# Detector.net
KiCad netlist of a schematic drawn in Altium Designer
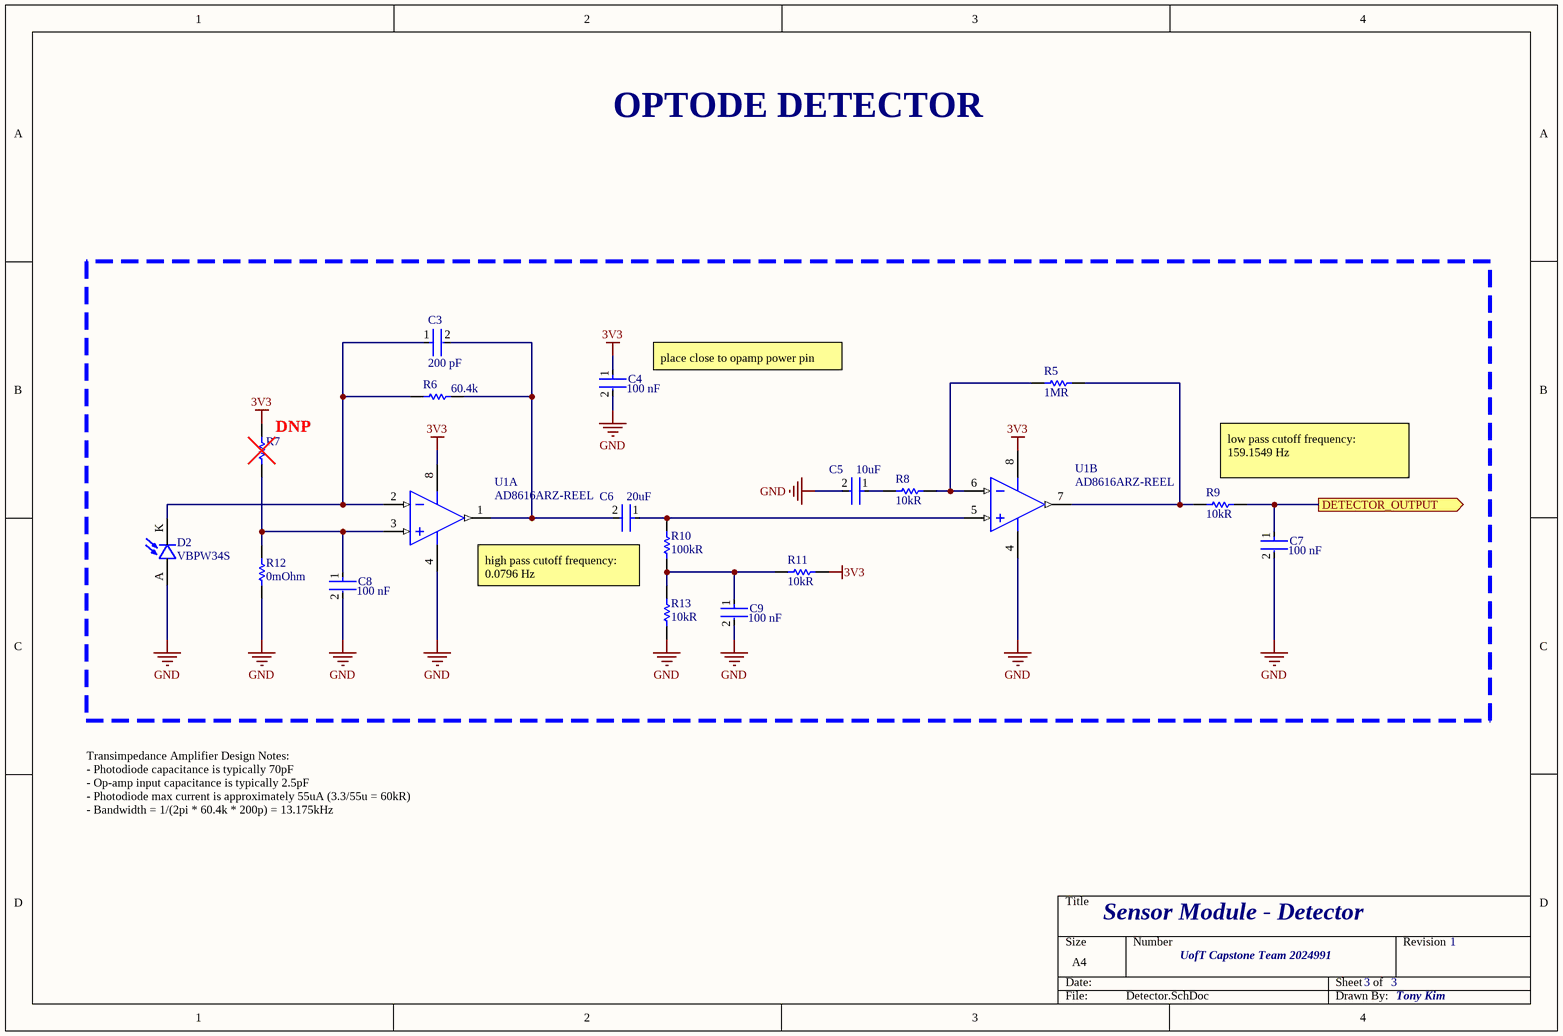
[diagram p0: Detector.SchDoc]

(export (version "E")
  (design (tool "Eeschema 10.0.6"))
  (components
    (comp (ref "C3")
      (value "C0603C201J5GACTU")
      (footprint "FP-C0603C-CF-MFG")
      (description "CAP CER 200PF 50V 5% NP0 0603")
      (fields
        (field (name "CAPACITANCE") "200 pF")
        (field (name "MANUFACTURER") "KEMET")
        (field (name "OCTOPART") "https://octopart.com/c0603c201j5gactu-kemet-9143917")
      )
      (libsource (lib "Altium Content Vault") (part "b4654b650e69147ec39a6b967a45e02"))
    )
    (comp (ref "C4")
      (value "CC0603KRX7R7BB104")
      (footprint "FP-CC0603-DA-MFG")
      (description "CAP CER 0.1UF 16V X7R 0603")
      (fields
        (field (name "OCTOPART") "https://octopart.com/cc0603krx7r7bb104-yageo-192941")
        (field (name "TOLERANCE") "0.1")
        (field (name "CAPACITANCE") "100 nF")
      )
      (libsource (lib "Altium Content Vault") (part "11868f565c42a9108669ba33697ecf6"))
    )
    (comp (ref "C5")
      (value "GRM188R60J106ME47D")
      (footprint "FP-GRM188-0_1-e0_2_0_55-IPC_C")
      (description "Chip Multilayer Ceramic Capacitors for General Purpose, 0603, 10uF, X5R, 15%, 20%, 6.3V")
      (fields
        (field (name "CAPACITANCE") "10uF")
        (field (name "VOLTAGE") "6.3V")
        (field (name "TOLERANCE") "20%")
      )
      (libsource (lib "Altium Content Vault") (part "02cd4be3c70576c341d710602a673aa"))
    )
    (comp (ref "C6")
      (value "GRM188R60J106ME47D")
      (footprint "FP-GRM188-0_1-e0_2_0_55-IPC_A")
      (description "Chip Multilayer Ceramic Capacitors for General Purpose, 0603, 10uF, X5R, 15%, 20%, 6.3V")
      (fields
        (field (name "CAPACITANCE") "20uF")
        (field (name "VOLTAGE") "6.3V")
        (field (name "TOLERANCE") "20%")
      )
      (libsource (lib "Altium Content Vault") (part "02cd4be3c70576c341d710602a673aa"))
    )
    (comp (ref "C7")
      (value "CC0603KRX7R7BB104")
      (footprint "FP-CC0603-DA-MFG")
      (description "CAP CER 0.1UF 16V X7R 0603")
      (fields
        (field (name "OCTOPART") "https://octopart.com/cc0603krx7r7bb104-yageo-192941")
        (field (name "TOLERANCE") "0.1")
        (field (name "CAPACITANCE") "100 nF")
      )
      (libsource (lib "Altium Content Vault") (part "11868f565c42a9108669ba33697ecf6"))
    )
    (comp (ref "C8")
      (value "CC0603KRX7R7BB104")
      (footprint "FP-CC0603-DA-MFG")
      (description "CAP CER 0.1UF 16V X7R 0603")
      (fields
        (field (name "OCTOPART") "https://octopart.com/cc0603krx7r7bb104-yageo-192941")
        (field (name "TOLERANCE") "0.1")
        (field (name "CAPACITANCE") "100 nF")
      )
      (libsource (lib "Altium Content Vault") (part "11868f565c42a9108669ba33697ecf6"))
    )
    (comp (ref "C9")
      (value "CC0603KRX7R7BB104")
      (footprint "FP-CC0603-DA-MFG")
      (description "CAP CER 0.1UF 16V X7R 0603")
      (fields
        (field (name "OCTOPART") "https://octopart.com/cc0603krx7r7bb104-yageo-192941")
        (field (name "TOLERANCE") "0.1")
        (field (name "CAPACITANCE") "100 nF")
      )
      (libsource (lib "Altium Content Vault") (part "11868f565c42a9108669ba33697ecf6"))
    )
    (comp (ref "D2")
      (value "VBPW34S")
      (footprint "PcbLib1:XDCR_VBPW34S")
      (description "Photodiode 940nm 100ns 130Â° 2-SMD, Gull Wing")
      (fields (field (name "MF") "Vishay"))
      (libsource (lib "SourceOptode") (part "VBPW34S"))
    )
    (comp (ref "R5")
      (value "RC0603FR-071ML")
      (footprint "RESC1608X55X25LL10T15")
      (description "Chip Resistor, 1 MOhm, +/- 1%, 100 mW, -55 to 155 degC, 0603 (1608 Metric), RoHS, Tape and Reel")
      (fields (field (name "TOLERANCE") "20%") (field (name "RESISTANCE") "1MR"))
      (libsource (lib "Altium Content Vault") (part "RES-2"))
    )
    (comp (ref "R6")
      (value "RC0603FR-0760K4L")
      (footprint "RESC1608X55X25ML10T15")
      (fields (field (name "MANUFACTURER") "Yageo") (field (name "RESISTANCE") "60.4k"))
      (libsource (lib "Altium Content Vault") (part "RES"))
    )
    (comp (ref "R7")
      (value "CRCW060310K0FKEA")
      (footprint "RESC1609X50X30NL8T20")
      (description "Chip Resistor, 10 KOhm, +/- 1%, 100 mW, -55 to 155 degC, 0603 (1608 Metric), RoHS, Tape and Reel")
      (fields (field (name "MANUFACTURER") "Vishay Semiconductor"))
      (libsource (lib "Altium Content Vault") (part "RES-2"))
    )
    (comp (ref "R8")
      (value "CRCW060310K0FKEA")
      (footprint "RESC1609X50X30NL8T20")
      (description "Chip Resistor, 10 KOhm, +/- 1%, 100 mW, -55 to 155 degC, 0603 (1608 Metric), RoHS, Tape and Reel")
      (fields (field (name "MANUFACTURER") "Vishay Semiconductor") (field (name "RESISTANCE") "10kR"))
      (libsource (lib "Altium Content Vault") (part "RES-2"))
    )
    (comp (ref "R9")
      (value "CRCW060310K0FKEA")
      (footprint "RESC1609X50X30NL8T20")
      (description "Chip Resistor, 10 KOhm, +/- 1%, 100 mW, -55 to 155 degC, 0603 (1608 Metric), RoHS, Tape and Reel")
      (fields (field (name "MANUFACTURER") "Vishay Semiconductor") (field (name "RESISTANCE") "10kR"))
      (libsource (lib "Altium Content Vault") (part "RES-2"))
    )
    (comp (ref "R10")
      (value "ERJ-3EKF1003V")
      (footprint "RESC1608X55X30ML15T15")
      (fields (field (name "MANUFACTURER") "Panasonic") (field (name "RESISTANCE") "100kR"))
      (libsource (lib "Altium Content Vault") (part "RES"))
    )
    (comp (ref "R11")
      (value "CRCW060310K0FKEA")
      (footprint "RESC1609X50X30NL8T20")
      (description "Chip Resistor, 10 KOhm, +/- 1%, 100 mW, -55 to 155 degC, 0603 (1608 Metric), RoHS, Tape and Reel")
      (fields (field (name "MANUFACTURER") "Vishay Semiconductor") (field (name "RESISTANCE") "10kR"))
      (libsource (lib "Altium Content Vault") (part "RES-2"))
    )
    (comp (ref "R12")
      (value "RC0603JR-070RL")
      (footprint "RESC1608X55X25ML10T15")
      (description "Chip Resistor, 0 Ohm, +/- 5%, 0.1 W, -55 to 155 degC, 0603 (1608 Metric), RoHS, Tape and Reel")
      (fields
        (field (name "TOLERANCE") "5%")
        (field (name "RESISTANCE") "0mOhm")
        (field (name "MANUFACTURER") "Yageo")
      )
      (libsource (lib "Altium Content Vault") (part "RES-2"))
    )
    (comp (ref "R13")
      (value "CRCW060310K0FKEA")
      (footprint "RESC1609X50X30NL8T20")
      (description "Chip Resistor, 10 KOhm, +/- 1%, 100 mW, -55 to 155 degC, 0603 (1608 Metric), RoHS, Tape and Reel")
      (fields (field (name "MANUFACTURER") "Vishay Semiconductor") (field (name "RESISTANCE") "10kR"))
      (libsource (lib "Altium Content Vault") (part "RES-2"))
    )
    (comp (ref "U1")
      (value "AD8616ARZ-REEL")
      (footprint "ADI-R-8_N")
      (fields (field (name "MANUFACTURER") "Analog Devices") (field (name "GENERIC PART NUMBER") "AD8616"))
      (libsource (lib "Altium Content Vault") (part "ADI-OP29X-R-8"))
    )
  )
  (nets
    (net (code "1") (name "/DETECTOR_OUTPUT") (class "Default")
      (node (ref "C7") (pin "1") (pinfunction "1_1") (pintype "passive"))
      (node (ref "R9") (pin "1") (pinfunction "1_1") (pintype "passive"))
    )
    (net (code "2") (name "3V3") (class "Default")
      (node (ref "C4") (pin "1") (pinfunction "1_1") (pintype "passive"))
      (node (ref "R11") (pin "2") (pinfunction "2_2") (pintype "passive"))
      (node (ref "R7") (pin "2") (pinfunction "2_2") (pintype "passive"))
      (node (ref "U1") (pin "8") (pinfunction "+V_8") (pintype "power_in"))
    )
    (net (code "3") (name "GND") (class "Default")
      (node (ref "C4") (pin "2") (pinfunction "2_2") (pintype "passive"))
      (node (ref "C5") (pin "2") (pinfunction "2_2") (pintype "passive"))
      (node (ref "C7") (pin "2") (pinfunction "2_2") (pintype "passive"))
      (node (ref "C8") (pin "2") (pinfunction "2_2") (pintype "passive"))
      (node (ref "C9") (pin "2") (pinfunction "2_2") (pintype "passive"))
      (node (ref "D2") (pin "A") (pinfunction "A_A") (pintype "passive"))
      (node (ref "R12") (pin "1") (pinfunction "1_1") (pintype "passive"))
      (node (ref "R13") (pin "1") (pinfunction "1_1") (pintype "passive"))
      (node (ref "U1") (pin "4") (pinfunction "-V_4") (pintype "power_in"))
    )
    (net (code "4") (name "Net-(C5-Pad1)") (class "Default")
      (node (ref "C5") (pin "1") (pinfunction "1_1") (pintype "passive"))
      (node (ref "R8") (pin "1") (pinfunction "1_1") (pintype "passive"))
    )
    (net (code "5") (name "Net-(C9-Pad1)") (class "Default")
      (node (ref "C9") (pin "1") (pinfunction "1_1") (pintype "passive"))
      (node (ref "R10") (pin "1") (pinfunction "1_1") (pintype "passive"))
      (node (ref "R11") (pin "1") (pinfunction "1_1") (pintype "passive"))
      (node (ref "R13") (pin "2") (pinfunction "2_2") (pintype "passive"))
    )
    (net (code "6") (name "Net-(D2-C)") (class "Default")
      (node (ref "C3") (pin "1") (pinfunction "1_1") (pintype "passive"))
      (node (ref "D2") (pin "K") (pinfunction "C_K") (pintype "passive"))
      (node (ref "R6") (pin "1") (pinfunction "1_1") (pintype "passive"))
      (node (ref "U1") (pin "2") (pinfunction "-IN_A_2") (pintype "input"))
    )
    (net (code "7") (name "Net-(U1A-+IN_A)") (class "Default")
      (node (ref "C8") (pin "1") (pinfunction "1_1") (pintype "passive"))
      (node (ref "R12") (pin "2") (pinfunction "2_2") (pintype "passive"))
      (node (ref "R7") (pin "1") (pinfunction "1_1") (pintype "passive"))
      (node (ref "U1") (pin "3") (pinfunction "+IN_A_3") (pintype "input"))
    )
    (net (code "8") (name "Net-(U1A-OUT_A)") (class "Default")
      (node (ref "C3") (pin "2") (pinfunction "2_2") (pintype "passive"))
      (node (ref "C6") (pin "2") (pinfunction "2_2") (pintype "passive"))
      (node (ref "R6") (pin "2") (pinfunction "2_2") (pintype "passive"))
      (node (ref "U1") (pin "1") (pinfunction "OUT_A_1") (pintype "output"))
    )
    (net (code "9") (name "Net-(U1B-+IN_B)") (class "Default")
      (node (ref "C6") (pin "1") (pinfunction "1_1") (pintype "passive"))
      (node (ref "R10") (pin "2") (pinfunction "2_2") (pintype "passive"))
      (node (ref "U1") (pin "5") (pinfunction "+IN_B_5") (pintype "input"))
    )
    (net (code "10") (name "Net-(U1B--IN_B)") (class "Default")
      (node (ref "R5") (pin "2") (pinfunction "2_2") (pintype "passive"))
      (node (ref "R8") (pin "2") (pinfunction "2_2") (pintype "passive"))
      (node (ref "U1") (pin "6") (pinfunction "-IN_B_6") (pintype "input"))
    )
    (net (code "11") (name "Net-(U1B-OUT_B)") (class "Default")
      (node (ref "R5") (pin "1") (pinfunction "1_1") (pintype "passive"))
      (node (ref "R9") (pin "2") (pinfunction "2_2") (pintype "passive"))
      (node (ref "U1") (pin "7") (pinfunction "OUT_B_7") (pintype "output"))
    )
  )
)
